# Block_Diagram.net
KiCad netlist of a schematic drawn in Altium Designer
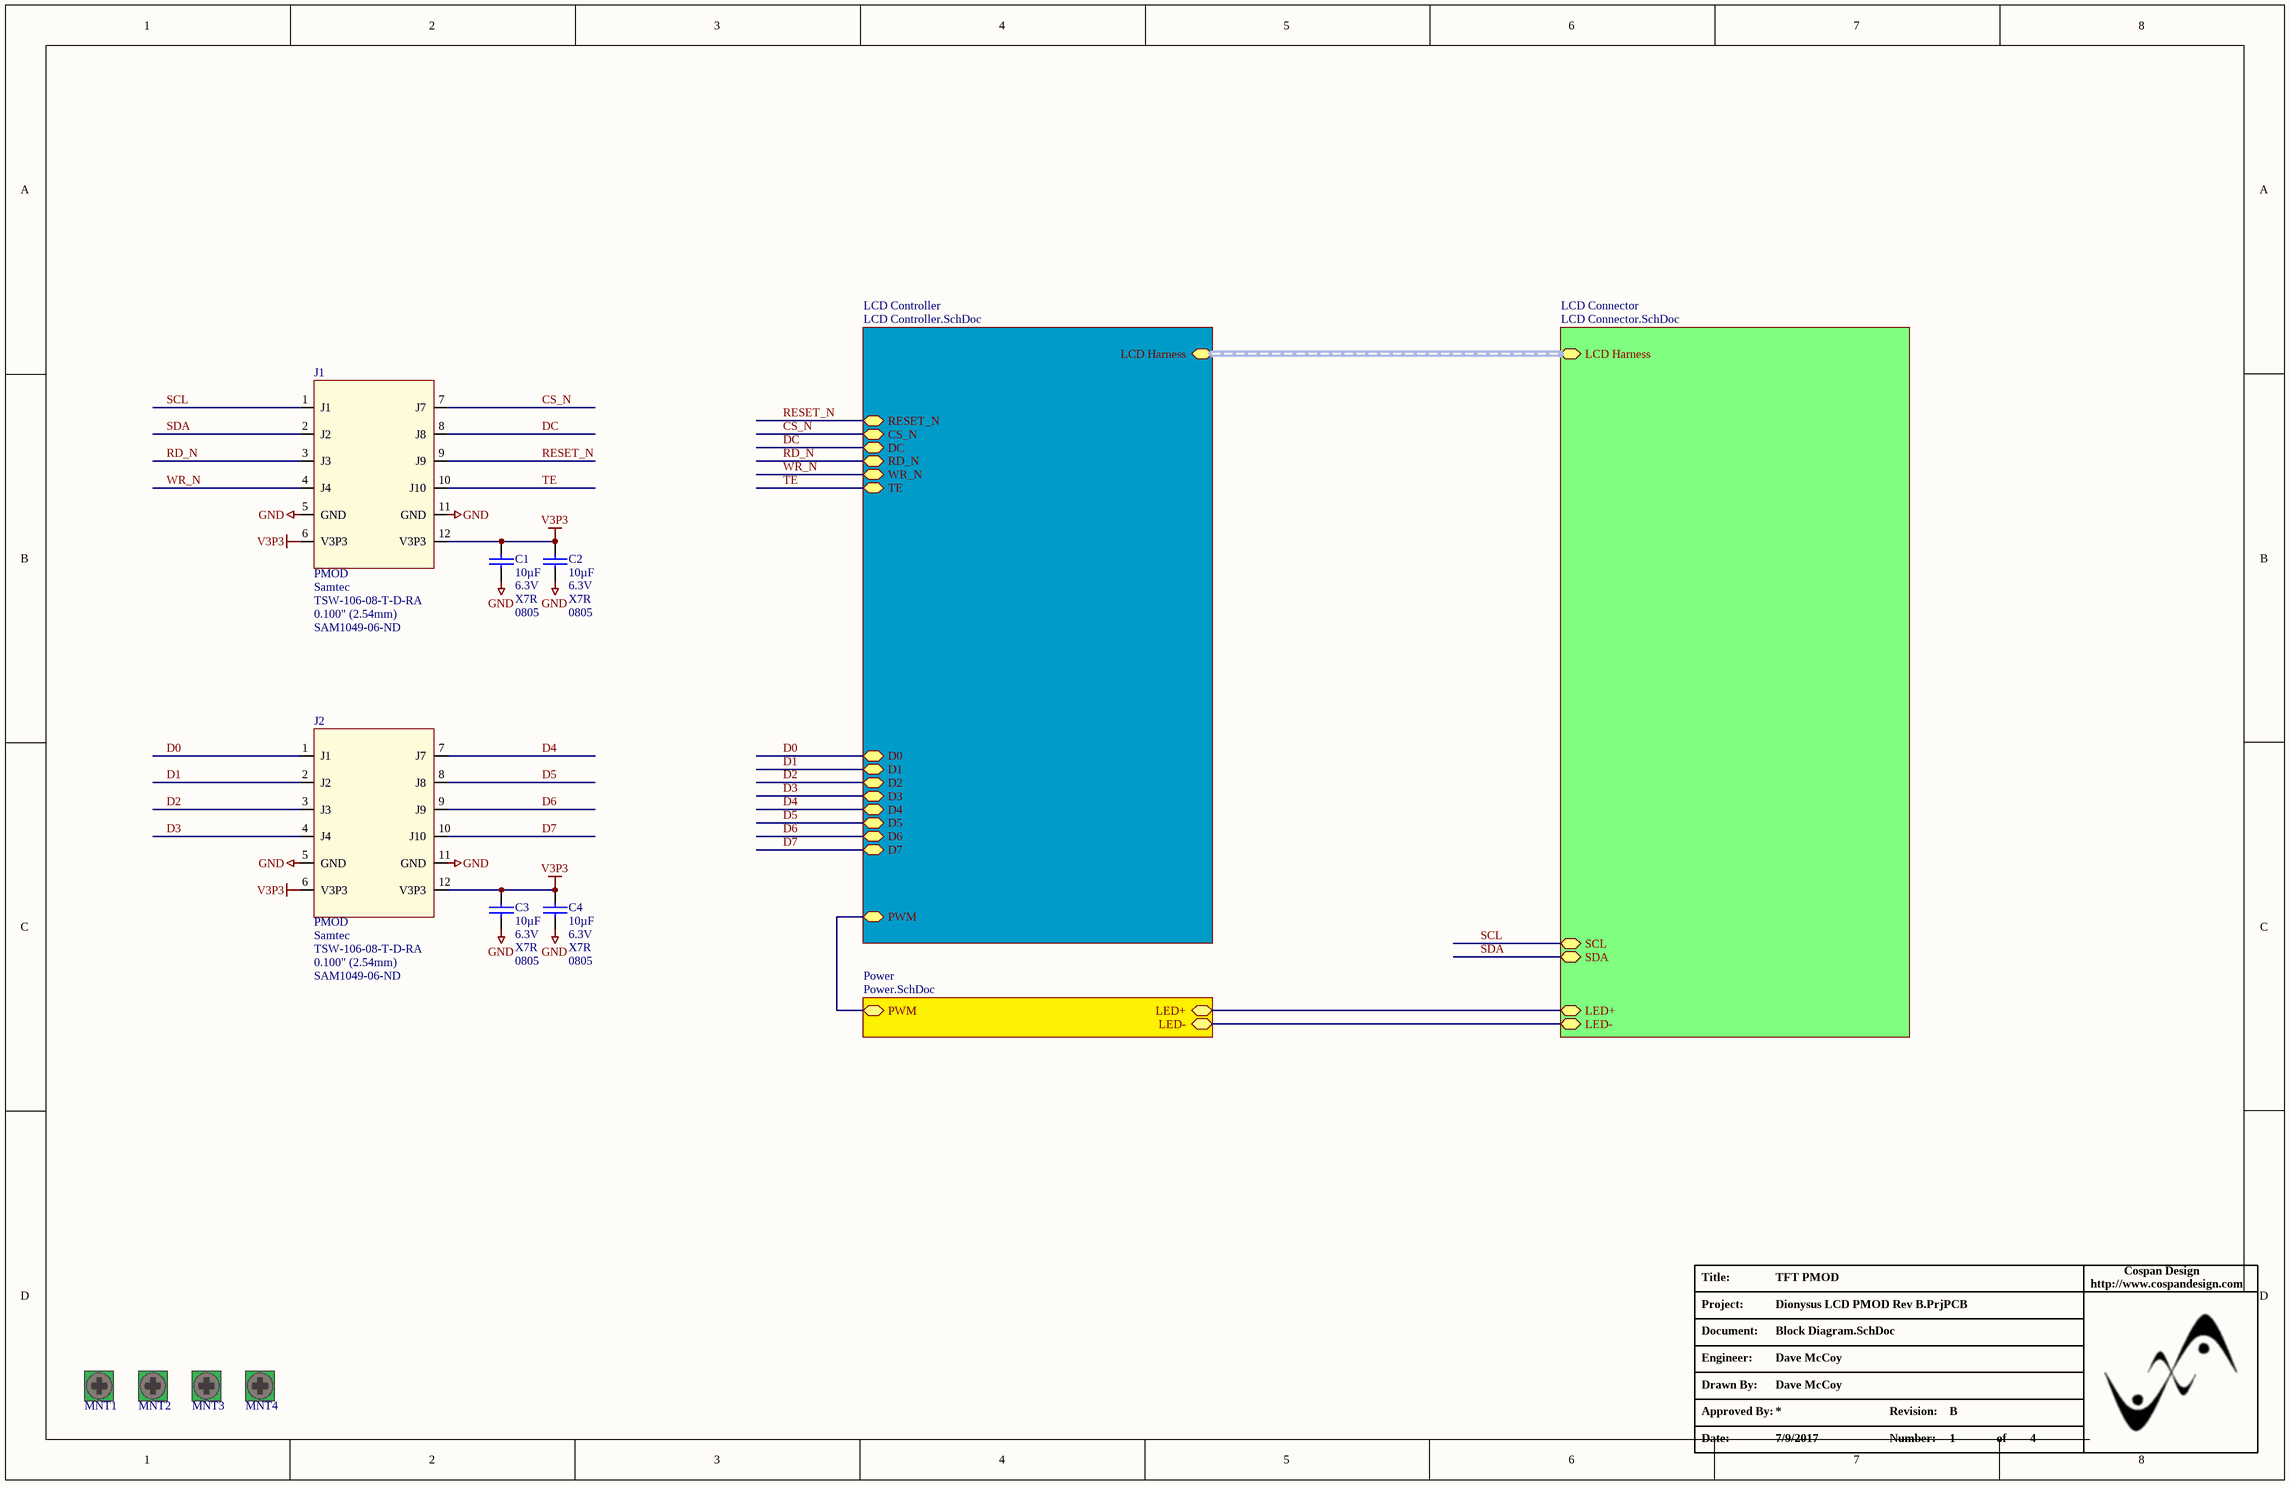
[diagram p0: Block Diagram.SchDoc]

(export (version "E")
  (design (tool "Eeschema 10.0.6"))
  (components
    (comp (ref "C1")
      (value "10uF")
      (footprint "C_ERA-0805")
      (description "CAP CER 10UF 6.3V X7R 10% 0805")
      (fields
        (field (name "MANUFACTURER") "Taiyo Yuden")
        (field (name "MANUFACTURER PART NUMBER") "JMK212BJ106KD-T")
        (field (name "CAPACITANCE") "10µF")
        (field (name "VOLTAGE - RATED") "6.3V")
        (field (name "TEMPERATURE COEFFICIENT") "X7R")
        (field (name "PACKAGE / CASE") "0805")
      )
      (libsource (lib "Main Library") (part "C_0805_10UF_6.3V"))
    )
    (comp (ref "C2")
      (value "10uF")
      (footprint "C_ERA-0805")
      (description "CAP CER 10UF 6.3V X7R 10% 0805")
      (fields
        (field (name "MANUFACTURER") "Taiyo Yuden")
        (field (name "MANUFACTURER PART NUMBER") "JMK212BJ106KD-T")
        (field (name "CAPACITANCE") "10µF")
        (field (name "VOLTAGE - RATED") "6.3V")
        (field (name "TEMPERATURE COEFFICIENT") "X7R")
        (field (name "PACKAGE / CASE") "0805")
      )
      (libsource (lib "Main Library") (part "C_0805_10UF_6.3V"))
    )
    (comp (ref "C3")
      (value "10uF")
      (footprint "C_ERA-0805")
      (description "CAP CER 10UF 6.3V X7R 10% 0805")
      (fields
        (field (name "MANUFACTURER") "Taiyo Yuden")
        (field (name "MANUFACTURER PART NUMBER") "JMK212BJ106KD-T")
        (field (name "CAPACITANCE") "10µF")
        (field (name "VOLTAGE - RATED") "6.3V")
        (field (name "TEMPERATURE COEFFICIENT") "X7R")
        (field (name "PACKAGE / CASE") "0805")
      )
      (libsource (lib "Main Library") (part "C_0805_10UF_6.3V"))
    )
    (comp (ref "C4")
      (value "10uF")
      (footprint "C_ERA-0805")
      (description "CAP CER 10UF 6.3V X7R 10% 0805")
      (fields
        (field (name "MANUFACTURER") "Taiyo Yuden")
        (field (name "MANUFACTURER PART NUMBER") "JMK212BJ106KD-T")
        (field (name "CAPACITANCE") "10µF")
        (field (name "VOLTAGE - RATED") "6.3V")
        (field (name "TEMPERATURE COEFFICIENT") "X7R")
        (field (name "PACKAGE / CASE") "0805")
      )
      (libsource (lib "Main Library") (part "C_0805_10UF_6.3V"))
    )
    (comp (ref "J1")
      (value "PMOD")
      (footprint "PMOD PERIPHERAL")
      (description "CONN HEADER 12PS .100 DL R/A TIN")
      (fields
        (field (name "MANUFACTURER") "Samtec")
        (field (name "MANUFACTURER PART NUMBER") "TSW-106-08-T-D-RA")
        (field (name "PITCH") "0.100\" (2.54mm)")
        (field (name "SUPPLIER PART NUMBER 1") "SAM1049-06-ND")
      )
      (libsource (lib "Main Library") (part "J_PMOD_PERIPH"))
    )
    (comp (ref "J2")
      (value "PMOD")
      (footprint "PMOD PERIPHERAL")
      (description "CONN HEADER 12PS .100 DL R/A TIN")
      (fields
        (field (name "MANUFACTURER") "Samtec")
        (field (name "MANUFACTURER PART NUMBER") "TSW-106-08-T-D-RA")
        (field (name "PITCH") "0.100\" (2.54mm)")
        (field (name "SUPPLIER PART NUMBER 1") "SAM1049-06-ND")
      )
      (libsource (lib "Main Library") (part "J_PMOD_PERIPH"))
    )
    (comp (ref "MNT1")
      (value "Mounting Hole")
      (footprint "MNT_4-40")
      (libsource (lib "Main Library") (part "MNT_440_HOLE"))
    )
    (comp (ref "MNT2")
      (value "Mounting Hole")
      (footprint "MNT_4-40")
      (libsource (lib "Main Library") (part "MNT_440_HOLE"))
    )
    (comp (ref "MNT3")
      (value "Mounting Hole")
      (footprint "MNT_4-40")
      (libsource (lib "Main Library") (part "MNT_440_HOLE"))
    )
    (comp (ref "MNT4")
      (value "Mounting Hole")
      (footprint "MNT_4-40")
      (libsource (lib "Main Library") (part "MNT_440_HOLE"))
    )
  )
  (nets
    (net (code "1") (name "/CS_N") (class "Default")
      (node (ref "J1") (pin "7") (pinfunction "J7_7") (pintype "passive"))
    )
    (net (code "2") (name "/D0") (class "Default")
      (node (ref "J2") (pin "1") (pinfunction "J1_1") (pintype "passive"))
    )
    (net (code "3") (name "/D1") (class "Default")
      (node (ref "J2") (pin "2") (pinfunction "J2_2") (pintype "passive"))
    )
    (net (code "4") (name "/D2") (class "Default")
      (node (ref "J2") (pin "3") (pinfunction "J3_3") (pintype "passive"))
    )
    (net (code "5") (name "/D3") (class "Default")
      (node (ref "J2") (pin "4") (pinfunction "J4_4") (pintype "passive"))
    )
    (net (code "6") (name "/D4") (class "Default")
      (node (ref "J2") (pin "7") (pinfunction "J7_7") (pintype "passive"))
    )
    (net (code "7") (name "/D5") (class "Default")
      (node (ref "J2") (pin "8") (pinfunction "J8_8") (pintype "passive"))
    )
    (net (code "8") (name "/D6") (class "Default")
      (node (ref "J2") (pin "9") (pinfunction "J9_9") (pintype "passive"))
    )
    (net (code "9") (name "/D7") (class "Default")
      (node (ref "J2") (pin "10") (pinfunction "J10_10") (pintype "passive"))
    )
    (net (code "10") (name "/DC") (class "Default")
      (node (ref "J1") (pin "8") (pinfunction "J8_8") (pintype "passive"))
    )
    (net (code "15") (name "/RD_N") (class "Default")
      (node (ref "J1") (pin "3") (pinfunction "J3_3") (pintype "passive"))
    )
    (net (code "16") (name "/RESET_N") (class "Default")
      (node (ref "J1") (pin "9") (pinfunction "J9_9") (pintype "passive"))
    )
    (net (code "17") (name "/SCL") (class "Default")
      (node (ref "J1") (pin "1") (pinfunction "J1_1") (pintype "passive"))
    )
    (net (code "18") (name "/SDA") (class "Default")
      (node (ref "J1") (pin "2") (pinfunction "J2_2") (pintype "passive"))
    )
    (net (code "19") (name "/TE") (class "Default")
      (node (ref "J1") (pin "10") (pinfunction "J10_10") (pintype "passive"))
    )
    (net (code "20") (name "/WR_N") (class "Default")
      (node (ref "J1") (pin "4") (pinfunction "J4_4") (pintype "passive"))
    )
    (net (code "21") (name "GND") (class "Default")
      (node (ref "C1") (pin "1") (pinfunction "1_1") (pintype "passive"))
      (node (ref "C2") (pin "1") (pinfunction "1_1") (pintype "passive"))
      (node (ref "C3") (pin "1") (pinfunction "1_1") (pintype "passive"))
      (node (ref "C4") (pin "1") (pinfunction "1_1") (pintype "passive"))
      (node (ref "J1") (pin "11") (pinfunction "GND_11") (pintype "passive"))
      (node (ref "J1") (pin "5") (pinfunction "GND_5") (pintype "passive"))
      (node (ref "J2") (pin "11") (pinfunction "GND_11") (pintype "passive"))
      (node (ref "J2") (pin "5") (pinfunction "GND_5") (pintype "passive"))
    )
    (net (code "22") (name "V3P3") (class "Default")
      (node (ref "C1") (pin "2") (pinfunction "2_2") (pintype "passive"))
      (node (ref "C2") (pin "2") (pinfunction "2_2") (pintype "passive"))
      (node (ref "C3") (pin "2") (pinfunction "2_2") (pintype "passive"))
      (node (ref "C4") (pin "2") (pinfunction "2_2") (pintype "passive"))
      (node (ref "J1") (pin "12") (pinfunction "V3P3_12") (pintype "passive"))
      (node (ref "J1") (pin "6") (pinfunction "V3P3_6") (pintype "passive"))
      (node (ref "J2") (pin "12") (pinfunction "V3P3_12") (pintype "passive"))
      (node (ref "J2") (pin "6") (pinfunction "V3P3_6") (pintype "passive"))
    )
  )
)
